# ALS.net
KiCad netlist of a schematic drawn in Altium Designer
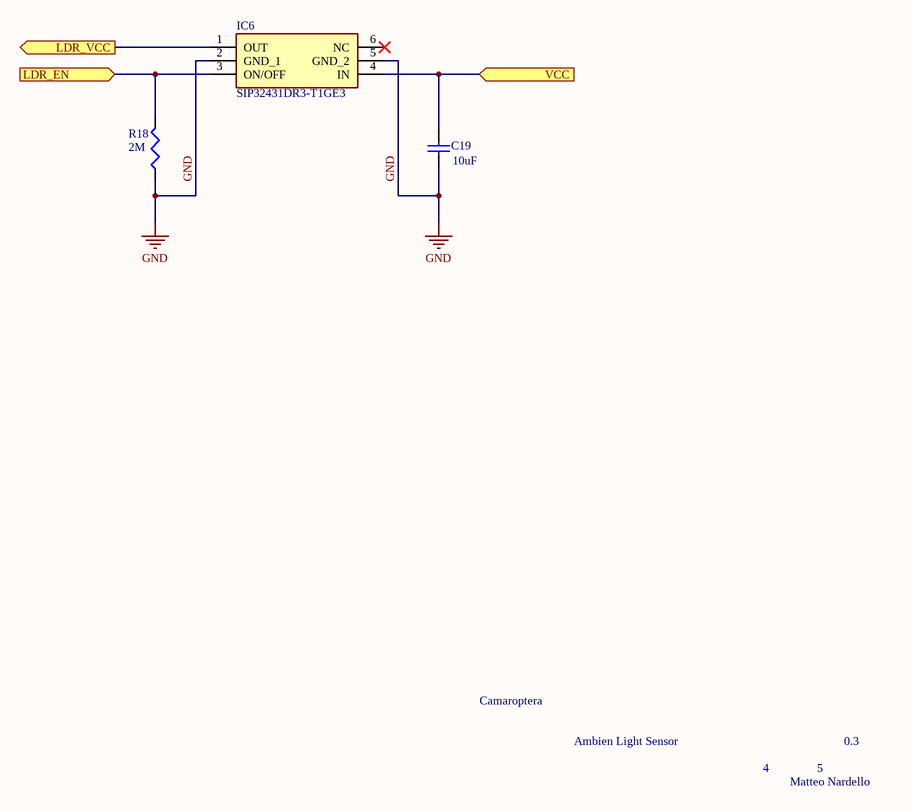
[diagram p0: ALS.SchDoc]

(export (version "E")
  (design (tool "Eeschema 10.0.6"))
  (components
    (comp (ref "C19")
      (value "10uF")
      (footprint "1608[0603]")
      (description "CAP CER 6.3V X5R/X7R 0603")
      (fields (field (name "Comment") "Cap") (field (name "PUBLISHER") "Altium Limited"))
      (libsource (lib "Miscellaneous Devices") (part "Cap"))
    )
    (comp (ref "IC6")
      (value "SIP32431DR3-T1GE3")
      (footprint "SamacSys:SOT65P210X110-6N")
      (description "10 pA, Ultra Low Leakage and Quiescent Current,\r\nLoad Switch with Reverse Blocking")
      (fields (field (name "MOUSER PART NUMBER") "781-SIP32431DR3-GE3"))
      (libsource (lib "*") (part "SIP32431DR3-T1GE3"))
    )
    (comp (ref "R18")
      (value "2M")
      (footprint "J1-0603")
      (description "RES 1/10W 1% 0603 SMD")
      (fields (field (name "Comment") "Res3") (field (name "PUBLISHER") "Altium Limited"))
      (libsource (lib "Miscellaneous Devices") (part "Res3"))
    )
  )
  (nets
    (net (code "1") (name "/LDR_EN") (class "Default")
      (node (ref "IC6") (pin "3") (pinfunction "ON/OFF_3") (pintype "passive"))
      (node (ref "R18") (pin "2") (pinfunction "2_2") (pintype "passive"))
    )
    (net (code "2") (name "/LDR_VCC") (class "Default")
      (node (ref "IC6") (pin "1") (pinfunction "OUT_1") (pintype "passive"))
    )
    (net (code "3") (name "/VCC") (class "Default")
      (node (ref "C19") (pin "2") (pinfunction "2_2") (pintype "passive"))
      (node (ref "IC6") (pin "4") (pinfunction "IN_4") (pintype "passive"))
    )
    (net (code "4") (name "GND") (class "Default")
      (node (ref "C19") (pin "1") (pinfunction "1_1") (pintype "passive"))
      (node (ref "IC6") (pin "2") (pinfunction "GND_1_2") (pintype "passive"))
      (node (ref "IC6") (pin "5") (pinfunction "GND_2_5") (pintype "passive"))
      (node (ref "R18") (pin "1") (pinfunction "1_1") (pintype "passive"))
    )
    (net (code "5") (name "unconnected-(IC6-NC-Pad6)") (class "Default")
      (node (ref "IC6") (pin "6") (pinfunction "NC_6") (pintype "passive+no_connect"))
    )
  )
)
